# 2_MCU.net
KiCad netlist of a schematic drawn in Altium Designer
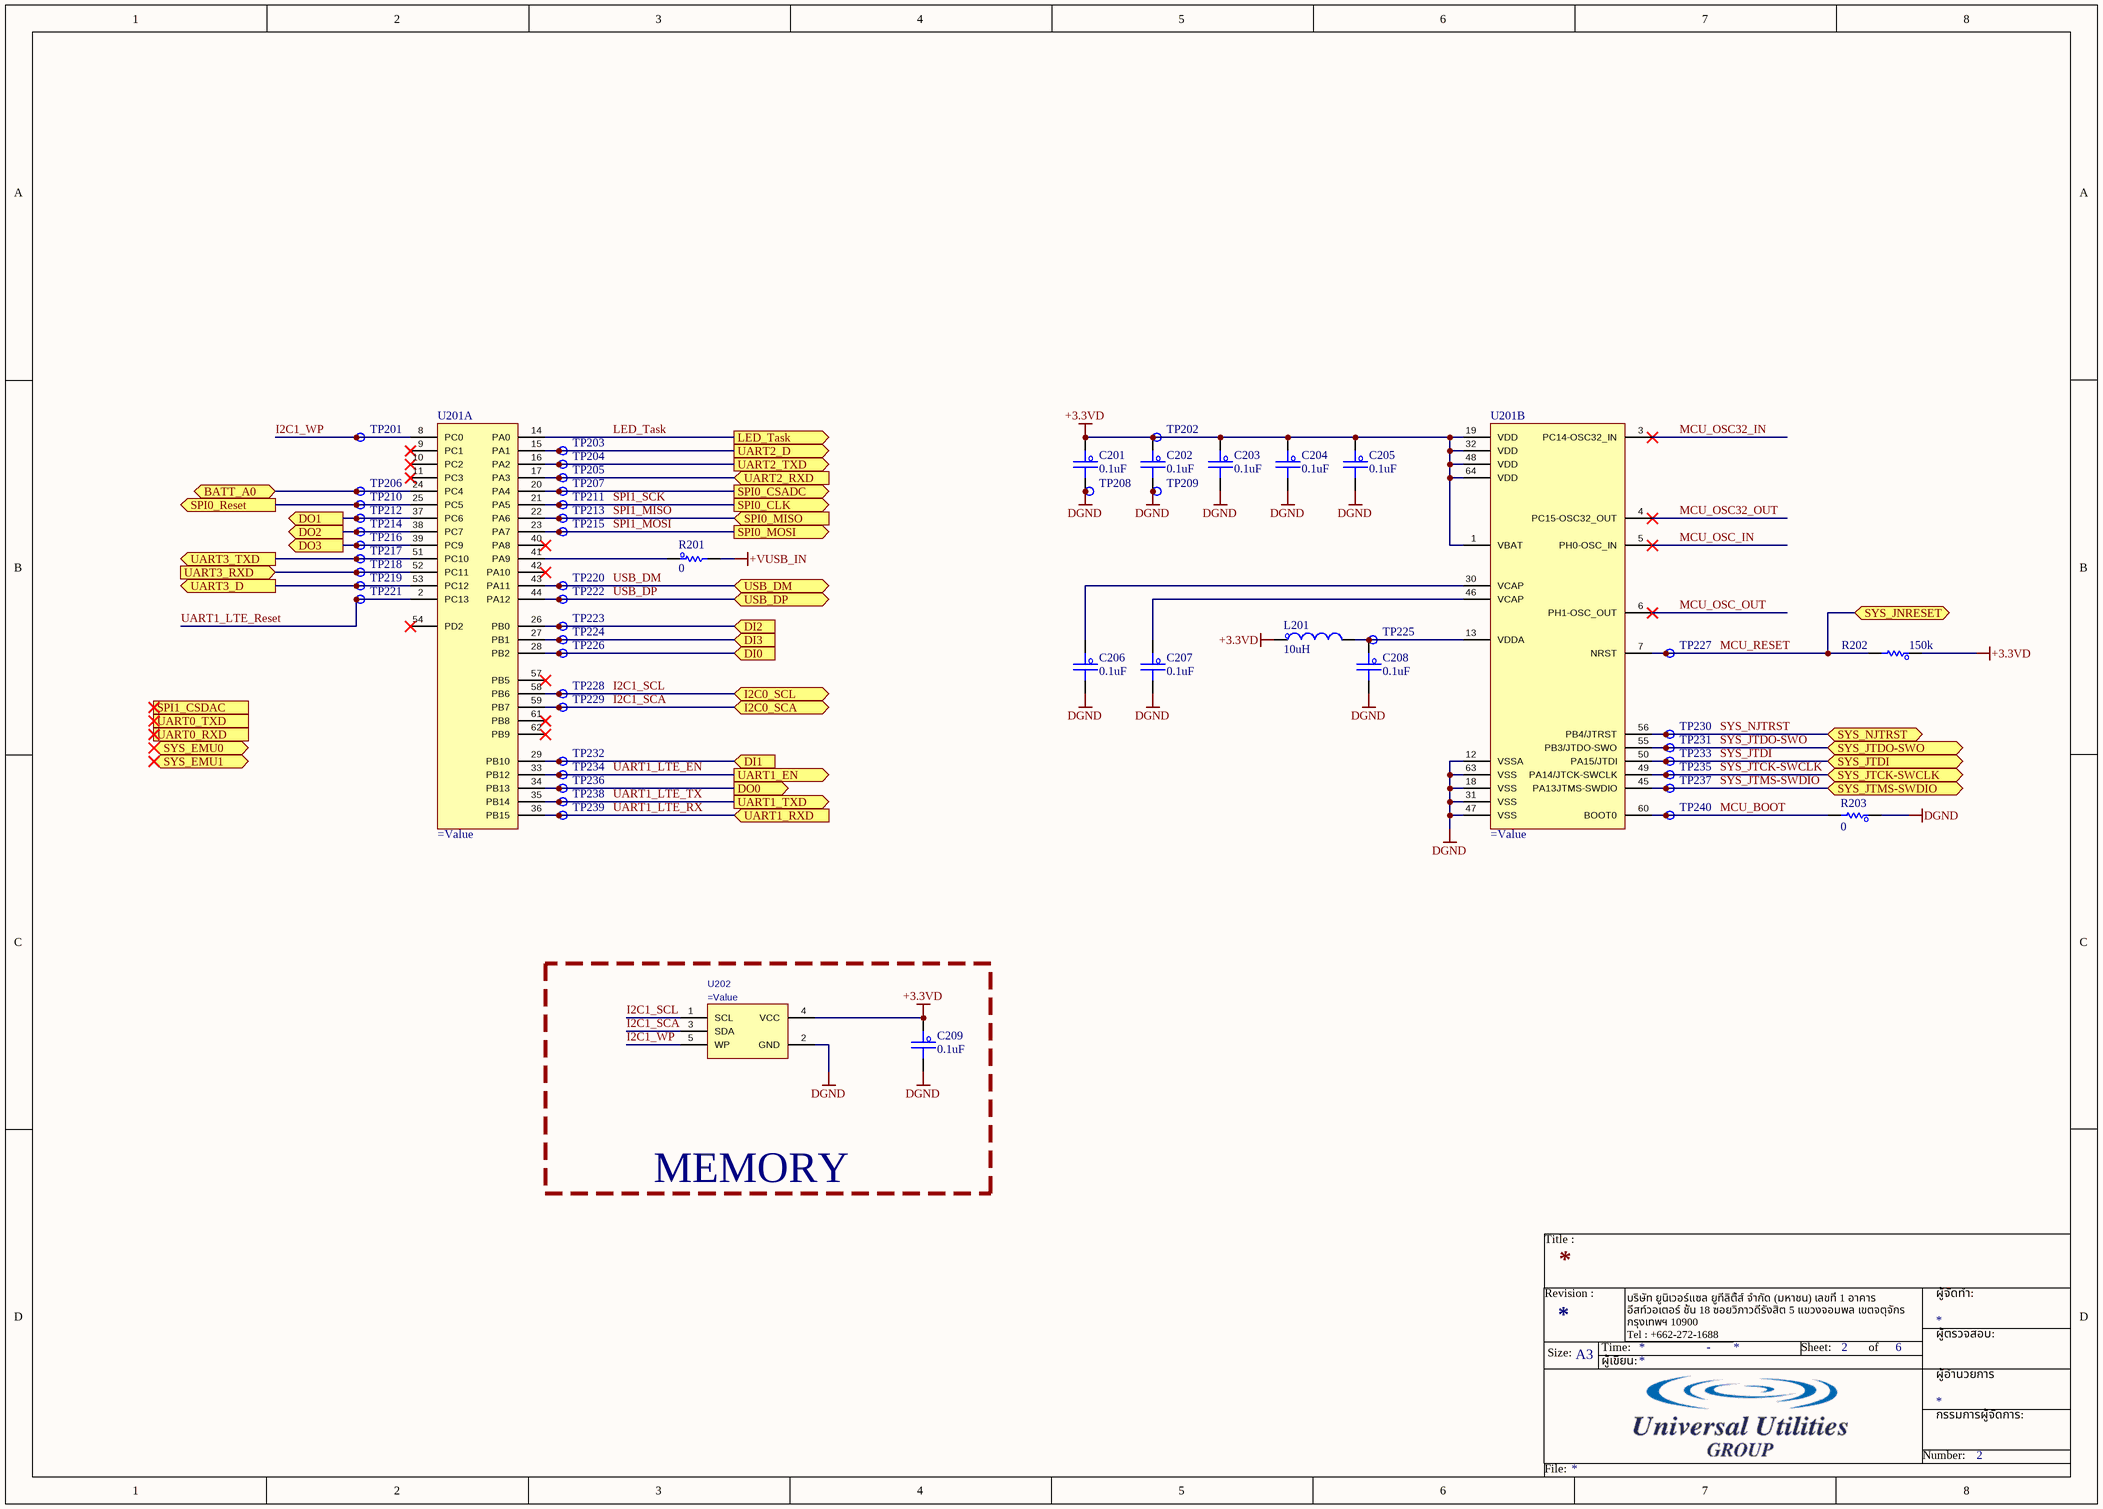
[diagram p0: 2_MCU.SchDoc]

(export (version "E")
  (design (tool "Eeschema 10.0.6"))
  (components
    (comp (ref "C201")
      (value "0.1uF")
      (footprint "C_0603")
      (description "CAP CER 0.1UF 50V X7R 0603")
      (fields (field (name "MANUFACTURER") "KEMET") (field (name "PARTNUMBER") "C0603C104K5RACTU"))
      (libsource (lib "UUSymbol") (part "C_Capacitor"))
    )
    (comp (ref "C202")
      (value "0.1uF")
      (footprint "C_0603")
      (description "CAP CER 0.1UF 50V X7R 0603")
      (fields (field (name "MANUFACTURER") "KEMET") (field (name "PARTNUMBER") "C0603C104K5RACTU"))
      (libsource (lib "UUSymbol") (part "C_Capacitor"))
    )
    (comp (ref "C203")
      (value "0.1uF")
      (footprint "C_0603")
      (description "CAP CER 0.1UF 50V X7R 0603")
      (fields (field (name "MANUFACTURER") "KEMET") (field (name "PARTNUMBER") "C0603C104K5RACTU"))
      (libsource (lib "UUSymbol") (part "C_Capacitor"))
    )
    (comp (ref "C204")
      (value "0.1uF")
      (footprint "C_0603")
      (description "CAP CER 0.1UF 50V X7R 0603")
      (fields (field (name "MANUFACTURER") "KEMET") (field (name "PARTNUMBER") "C0603C104K5RACTU"))
      (libsource (lib "UUSymbol") (part "C_Capacitor"))
    )
    (comp (ref "C205")
      (value "0.1uF")
      (footprint "C_0603")
      (description "CAP CER 0.1UF 50V X7R 0603")
      (fields (field (name "MANUFACTURER") "KEMET") (field (name "PARTNUMBER") "C0603C104K5RACTU"))
      (libsource (lib "UUSymbol") (part "C_Capacitor"))
    )
    (comp (ref "C206")
      (value "0.1uF")
      (footprint "C_0603")
      (description "CAP CER 0.1UF 50V X7R 0603")
      (fields (field (name "MANUFACTURER") "KEMET") (field (name "PARTNUMBER") "C0603C104K5RACTU"))
      (libsource (lib "UUSymbol") (part "C_Capacitor"))
    )
    (comp (ref "C207")
      (value "0.1uF")
      (footprint "C_0603")
      (description "CAP CER 0.1UF 50V X7R 0603")
      (fields (field (name "MANUFACTURER") "KEMET") (field (name "PARTNUMBER") "C0603C104K5RACTU"))
      (libsource (lib "UUSymbol") (part "C_Capacitor"))
    )
    (comp (ref "C208")
      (value "0.1uF")
      (footprint "C_0603")
      (description "CAP CER 0.1UF 50V X7R 0603")
      (fields (field (name "MANUFACTURER") "KEMET") (field (name "PARTNUMBER") "C0603C104K5RACTU"))
      (libsource (lib "UUSymbol") (part "C_Capacitor"))
    )
    (comp (ref "C209")
      (value "0.1uF")
      (footprint "C_0603")
      (description "CAP CER 0.1UF 50V X7R 0603")
      (fields (field (name "MANUFACTURER") "KEMET") (field (name "PARTNUMBER") "C0603C104K5RACTU"))
      (libsource (lib "UUSymbol") (part "C_Capacitor"))
    )
    (comp (ref "L201")
      (value "10uH")
      (footprint "L_0603")
      (description "10µH Shielded Multilayer Inductor 250mA 1.05Ohm 0603 (1608 Metric)")
      (fields (field (name "MANUFACTURER") "TDK Corporation") (field (name "PARTNUMBER") "MLZ1608M100WT000"))
      (libsource (lib "UUSymbol") (part "L_Inductor"))
    )
    (comp (ref "R201")
      (value "0")
      (footprint "R_0603")
      (description "RES SMD 0 OHM JUMP 1/10W 0603")
      (fields (field (name "MANUFACTURER") "Vishay Dale") (field (name "PARTNUMBER") "CRCW06030000Z0EBC"))
      (libsource (lib "UUSymbol") (part "R_Resister"))
    )
    (comp (ref "R202")
      (value "150k")
      (footprint "R_0603")
      (description "RES SMD 150K OHM 1% 1/10W 0603")
      (fields (field (name "MANUFACTURER") "Vishay Dale") (field (name "PARTNUMBER") "CRCW0603150KFKEAC"))
      (libsource (lib "UUSymbol") (part "R_Resister"))
    )
    (comp (ref "R203")
      (value "0")
      (footprint "R_0603")
      (description "RES SMD 0 OHM JUMP 1/10W 0603")
      (fields (field (name "MANUFACTURER") "Vishay Dale") (field (name "PARTNUMBER") "CRCW06030000Z0EBC"))
      (libsource (lib "UUSymbol") (part "R_Resister"))
    )
    (comp (ref "TP201")
      (value "~")
      (footprint "TP_Testpoint")
      (description "TestPoint")
      (libsource (lib "UUSymbol") (part "TP_TestPoint"))
    )
    (comp (ref "TP202")
      (value "~")
      (footprint "TP_Testpoint")
      (description "TestPoint")
      (libsource (lib "UUSymbol") (part "TP_TestPoint"))
    )
    (comp (ref "TP203")
      (value "~")
      (footprint "TP_Testpoint")
      (description "TestPoint")
      (libsource (lib "UUSymbol") (part "TP_TestPoint"))
    )
    (comp (ref "TP204")
      (value "~")
      (footprint "TP_Testpoint")
      (description "TestPoint")
      (libsource (lib "UUSymbol") (part "TP_TestPoint"))
    )
    (comp (ref "TP205")
      (value "~")
      (footprint "TP_Testpoint")
      (description "TestPoint")
      (libsource (lib "UUSymbol") (part "TP_TestPoint"))
    )
    (comp (ref "TP206")
      (value "~")
      (footprint "TP_Testpoint")
      (description "TestPoint")
      (libsource (lib "UUSymbol") (part "TP_TestPoint"))
    )
    (comp (ref "TP207")
      (value "~")
      (footprint "TP_Testpoint")
      (description "TestPoint")
      (libsource (lib "UUSymbol") (part "TP_TestPoint"))
    )
    (comp (ref "TP208")
      (value "~")
      (footprint "TP_Testpoint")
      (description "TestPoint")
      (libsource (lib "UUSymbol") (part "TP_TestPoint"))
    )
    (comp (ref "TP209")
      (value "~")
      (footprint "TP_Testpoint")
      (description "TestPoint")
      (libsource (lib "UUSymbol") (part "TP_TestPoint"))
    )
    (comp (ref "TP210")
      (value "~")
      (footprint "TP_Testpoint")
      (description "TestPoint")
      (libsource (lib "UUSymbol") (part "TP_TestPoint"))
    )
    (comp (ref "TP211")
      (value "~")
      (footprint "TP_Testpoint")
      (description "TestPoint")
      (libsource (lib "UUSymbol") (part "TP_TestPoint"))
    )
    (comp (ref "TP212")
      (value "~")
      (footprint "TP_Testpoint")
      (description "TestPoint")
      (libsource (lib "UUSymbol") (part "TP_TestPoint"))
    )
    (comp (ref "TP213")
      (value "~")
      (footprint "TP_Testpoint")
      (description "TestPoint")
      (libsource (lib "UUSymbol") (part "TP_TestPoint"))
    )
    (comp (ref "TP214")
      (value "~")
      (footprint "TP_Testpoint")
      (description "TestPoint")
      (libsource (lib "UUSymbol") (part "TP_TestPoint"))
    )
    (comp (ref "TP215")
      (value "~")
      (footprint "TP_Testpoint")
      (description "TestPoint")
      (libsource (lib "UUSymbol") (part "TP_TestPoint"))
    )
    (comp (ref "TP216")
      (value "~")
      (footprint "TP_Testpoint")
      (description "TestPoint")
      (libsource (lib "UUSymbol") (part "TP_TestPoint"))
    )
    (comp (ref "TP217")
      (value "~")
      (footprint "TP_Testpoint")
      (description "TestPoint")
      (libsource (lib "UUSymbol") (part "TP_TestPoint"))
    )
    (comp (ref "TP218")
      (value "~")
      (footprint "TP_Testpoint")
      (description "TestPoint")
      (libsource (lib "UUSymbol") (part "TP_TestPoint"))
    )
    (comp (ref "TP219")
      (value "~")
      (footprint "TP_Testpoint")
      (description "TestPoint")
      (libsource (lib "UUSymbol") (part "TP_TestPoint"))
    )
    (comp (ref "TP220")
      (value "~")
      (footprint "TP_Testpoint")
      (description "TestPoint")
      (libsource (lib "UUSymbol") (part "TP_TestPoint"))
    )
    (comp (ref "TP221")
      (value "~")
      (footprint "TP_Testpoint")
      (description "TestPoint")
      (libsource (lib "UUSymbol") (part "TP_TestPoint"))
    )
    (comp (ref "TP222")
      (value "~")
      (footprint "TP_Testpoint")
      (description "TestPoint")
      (libsource (lib "UUSymbol") (part "TP_TestPoint"))
    )
    (comp (ref "TP223")
      (value "~")
      (footprint "TP_Testpoint")
      (description "TestPoint")
      (libsource (lib "UUSymbol") (part "TP_TestPoint"))
    )
    (comp (ref "TP224")
      (value "~")
      (footprint "TP_Testpoint")
      (description "TestPoint")
      (libsource (lib "UUSymbol") (part "TP_TestPoint"))
    )
    (comp (ref "TP225")
      (value "~")
      (footprint "TP_Testpoint")
      (description "TestPoint")
      (libsource (lib "UUSymbol") (part "TP_TestPoint"))
    )
    (comp (ref "TP226")
      (value "~")
      (footprint "TP_Testpoint")
      (description "TestPoint")
      (libsource (lib "UUSymbol") (part "TP_TestPoint"))
    )
    (comp (ref "TP227")
      (value "~")
      (footprint "TP_Testpoint")
      (description "TestPoint")
      (libsource (lib "UUSymbol") (part "TP_TestPoint"))
    )
    (comp (ref "TP228")
      (value "~")
      (footprint "TP_Testpoint")
      (description "TestPoint")
      (libsource (lib "UUSymbol") (part "TP_TestPoint"))
    )
    (comp (ref "TP229")
      (value "~")
      (footprint "TP_Testpoint")
      (description "TestPoint")
      (libsource (lib "UUSymbol") (part "TP_TestPoint"))
    )
    (comp (ref "TP230")
      (value "~")
      (footprint "TP_Testpoint")
      (description "TestPoint")
      (libsource (lib "UUSymbol") (part "TP_TestPoint"))
    )
    (comp (ref "TP231")
      (value "~")
      (footprint "TP_Testpoint")
      (description "TestPoint")
      (libsource (lib "UUSymbol") (part "TP_TestPoint"))
    )
    (comp (ref "TP232")
      (value "~")
      (footprint "TP_Testpoint")
      (description "TestPoint")
      (libsource (lib "UUSymbol") (part "TP_TestPoint"))
    )
    (comp (ref "TP233")
      (value "~")
      (footprint "TP_Testpoint")
      (description "TestPoint")
      (libsource (lib "UUSymbol") (part "TP_TestPoint"))
    )
    (comp (ref "TP234")
      (value "~")
      (footprint "TP_Testpoint")
      (description "TestPoint")
      (libsource (lib "UUSymbol") (part "TP_TestPoint"))
    )
    (comp (ref "TP235")
      (value "~")
      (footprint "TP_Testpoint")
      (description "TestPoint")
      (libsource (lib "UUSymbol") (part "TP_TestPoint"))
    )
    (comp (ref "TP236")
      (value "~")
      (footprint "TP_Testpoint")
      (description "TestPoint")
      (libsource (lib "UUSymbol") (part "TP_TestPoint"))
    )
    (comp (ref "TP237")
      (value "~")
      (footprint "TP_Testpoint")
      (description "TestPoint")
      (libsource (lib "UUSymbol") (part "TP_TestPoint"))
    )
    (comp (ref "TP238")
      (value "~")
      (footprint "TP_Testpoint")
      (description "TestPoint")
      (libsource (lib "UUSymbol") (part "TP_TestPoint"))
    )
    (comp (ref "TP239")
      (value "~")
      (footprint "TP_Testpoint")
      (description "TestPoint")
      (libsource (lib "UUSymbol") (part "TP_TestPoint"))
    )
    (comp (ref "TP240")
      (value "~")
      (footprint "TP_Testpoint")
      (description "TestPoint")
      (libsource (lib "UUSymbol") (part "TP_TestPoint"))
    )
    (comp (ref "U201")
      (value "~")
      (footprint "LQFP64")
      (description "IC MCU 32BIT 1376KB FLSH 64LQFP")
      (fields (field (name "PARTNUMBER") "STM32H7A3RGT6") (field (name "MANUFACTURER") "STMicroelectronics"))
      (libsource (lib "UUSymbol") (part "IC_MCU_STM32H7A3RGT6"))
    )
    (comp (ref "U202")
      (value "~")
      (footprint "SOT65P210X110-5N")
      (description "IC EEPROM 2KBIT I2C SC70-5")
      (fields
        (field (name "MANUFACTURER") "Microchip Technology")
        (field (name "PARTNUMBER") "24AA02HT-I/LT")
      )
      (libsource (lib "UUSymbol") (part "IC_MEM_24AA02HT"))
    )
  )
  (nets
    (net (code "1") (name "+3.3VD") (class "Default")
      (node (ref "C201") (pin "1") (pinfunction "1_1") (pintype "passive"))
      (node (ref "C202") (pin "1") (pinfunction "1_1") (pintype "passive"))
      (node (ref "C203") (pin "1") (pinfunction "1_1") (pintype "passive"))
      (node (ref "C204") (pin "1") (pinfunction "1_1") (pintype "passive"))
      (node (ref "C205") (pin "1") (pinfunction "1_1") (pintype "passive"))
      (node (ref "C209") (pin "1") (pinfunction "1_1") (pintype "passive"))
      (node (ref "L201") (pin "1") (pinfunction "1_1") (pintype "passive"))
      (node (ref "R202") (pin "1") (pinfunction "1_1") (pintype "passive"))
      (node (ref "TP202") (pin "1") (pinfunction "1_1") (pintype "passive"))
      (node (ref "U201") (pin "1") (pinfunction "VBAT_1") (pintype "passive"))
      (node (ref "U201") (pin "19") (pinfunction "VDD_19") (pintype "passive"))
      (node (ref "U201") (pin "32") (pinfunction "VDD_32") (pintype "passive"))
      (node (ref "U201") (pin "48") (pinfunction "VDD_48") (pintype "passive"))
      (node (ref "U201") (pin "64") (pinfunction "VDD_64") (pintype "passive"))
      (node (ref "U202") (pin "4") (pinfunction "VCC_4") (pintype "passive"))
    )
    (net (code "2") (name "+VUSB_IN") (class "Default")
      (node (ref "R201") (pin "2") (pinfunction "2_2") (pintype "passive"))
    )
    (net (code "3") (name "/BATT_A0") (class "Default")
      (node (ref "TP206") (pin "1") (pinfunction "1_1") (pintype "passive"))
      (node (ref "U201") (pin "24") (pinfunction "PC4_24") (pintype "passive"))
    )
    (net (code "4") (name "/DI0") (class "Default")
      (node (ref "TP226") (pin "1") (pinfunction "1_1") (pintype "passive"))
      (node (ref "U201") (pin "28") (pinfunction "PB2_28") (pintype "passive"))
    )
    (net (code "5") (name "/DI1") (class "Default")
      (node (ref "TP232") (pin "1") (pinfunction "1_1") (pintype "passive"))
      (node (ref "U201") (pin "29") (pinfunction "PB10_29") (pintype "passive"))
    )
    (net (code "6") (name "/DI2") (class "Default")
      (node (ref "TP223") (pin "1") (pinfunction "1_1") (pintype "passive"))
      (node (ref "U201") (pin "26") (pinfunction "PB0_26") (pintype "passive"))
    )
    (net (code "7") (name "/DI3") (class "Default")
      (node (ref "TP224") (pin "1") (pinfunction "1_1") (pintype "passive"))
      (node (ref "U201") (pin "27") (pinfunction "PB1_27") (pintype "passive"))
    )
    (net (code "8") (name "/DO0") (class "Default")
      (node (ref "TP236") (pin "1") (pinfunction "1_1") (pintype "passive"))
      (node (ref "U201") (pin "34") (pinfunction "PB13_34") (pintype "passive"))
    )
    (net (code "9") (name "/DO1") (class "Default")
      (node (ref "TP212") (pin "1") (pinfunction "1_1") (pintype "passive"))
      (node (ref "U201") (pin "37") (pinfunction "PC6_37") (pintype "passive"))
    )
    (net (code "10") (name "/DO2") (class "Default")
      (node (ref "TP214") (pin "1") (pinfunction "1_1") (pintype "passive"))
      (node (ref "U201") (pin "38") (pinfunction "PC7_38") (pintype "passive"))
    )
    (net (code "11") (name "/DO3") (class "Default")
      (node (ref "TP216") (pin "1") (pinfunction "1_1") (pintype "passive"))
      (node (ref "U201") (pin "39") (pinfunction "PC9_39") (pintype "passive"))
    )
    (net (code "12") (name "/I2C1_SCA") (class "Default")
      (node (ref "TP229") (pin "1") (pinfunction "1_1") (pintype "passive"))
      (node (ref "U201") (pin "59") (pinfunction "PB7_59") (pintype "passive"))
      (node (ref "U202") (pin "3") (pinfunction "SDA_3") (pintype "passive"))
    )
    (net (code "13") (name "/I2C1_SCL") (class "Default")
      (node (ref "TP228") (pin "1") (pinfunction "1_1") (pintype "passive"))
      (node (ref "U201") (pin "58") (pinfunction "PB6_58") (pintype "passive"))
      (node (ref "U202") (pin "1") (pinfunction "SCL_1") (pintype "passive"))
    )
    (net (code "14") (name "/I2C1_WP") (class "Default")
      (node (ref "TP201") (pin "1") (pinfunction "1_1") (pintype "passive"))
      (node (ref "U201") (pin "8") (pinfunction "PC0_8") (pintype "passive"))
      (node (ref "U202") (pin "5") (pinfunction "WP_5") (pintype "passive"))
    )
    (net (code "15") (name "/LED_Task") (class "Default")
      (node (ref "U201") (pin "14") (pinfunction "PA0_14") (pintype "passive"))
    )
    (net (code "16") (name "/MCU_BOOT") (class "Default")
      (node (ref "R203") (pin "2") (pinfunction "2_2") (pintype "passive"))
      (node (ref "TP240") (pin "1") (pinfunction "1_1") (pintype "passive"))
      (node (ref "U201") (pin "60") (pinfunction "BOOT0_60") (pintype "passive"))
    )
    (net (code "17") (name "/MCU_OSC32_IN") (class "Default")
      (node (ref "U201") (pin "3") (pinfunction "PC14-OSC32_IN_3") (pintype "passive+no_connect"))
    )
    (net (code "18") (name "/MCU_OSC32_OUT") (class "Default")
      (node (ref "U201") (pin "4") (pinfunction "PC15-OSC32_OUT_4") (pintype "passive+no_connect"))
    )
    (net (code "19") (name "/MCU_OSC_IN") (class "Default")
      (node (ref "U201") (pin "5") (pinfunction "PH0-OSC_IN_5") (pintype "passive+no_connect"))
    )
    (net (code "20") (name "/MCU_OSC_OUT") (class "Default")
      (node (ref "U201") (pin "6") (pinfunction "PH1-OSC_OUT_6") (pintype "passive+no_connect"))
    )
    (net (code "21") (name "/MCU_RESET") (class "Default")
      (node (ref "R202") (pin "2") (pinfunction "2_2") (pintype "passive"))
      (node (ref "TP227") (pin "1") (pinfunction "1_1") (pintype "passive"))
      (node (ref "U201") (pin "7") (pinfunction "NRST_7") (pintype "passive"))
    )
    (net (code "22") (name "/SPI0_CSADC") (class "Default")
      (node (ref "TP207") (pin "1") (pinfunction "1_1") (pintype "passive"))
      (node (ref "U201") (pin "20") (pinfunction "PA4_20") (pintype "passive"))
    )
    (net (code "23") (name "/SPI0_Reset") (class "Default")
      (node (ref "TP210") (pin "1") (pinfunction "1_1") (pintype "passive"))
      (node (ref "U201") (pin "25") (pinfunction "PC5_25") (pintype "passive"))
    )
    (net (code "25") (name "/SPI1_MISO") (class "Default")
      (node (ref "TP213") (pin "1") (pinfunction "1_1") (pintype "passive"))
      (node (ref "U201") (pin "22") (pinfunction "PA6_22") (pintype "passive"))
    )
    (net (code "26") (name "/SPI1_MOSI") (class "Default")
      (node (ref "TP215") (pin "1") (pinfunction "1_1") (pintype "passive"))
      (node (ref "U201") (pin "23") (pinfunction "PA7_23") (pintype "passive"))
    )
    (net (code "27") (name "/SPI1_SCK") (class "Default")
      (node (ref "TP211") (pin "1") (pinfunction "1_1") (pintype "passive"))
      (node (ref "U201") (pin "21") (pinfunction "PA5_21") (pintype "passive"))
    )
    (net (code "30") (name "/SYS_JTCK-SWCLK") (class "Default")
      (node (ref "TP235") (pin "1") (pinfunction "1_1") (pintype "passive"))
      (node (ref "U201") (pin "49") (pinfunction "PA14/JTCK-SWCLK_49") (pintype "passive"))
    )
    (net (code "31") (name "/SYS_JTDI") (class "Default")
      (node (ref "TP233") (pin "1") (pinfunction "1_1") (pintype "passive"))
      (node (ref "U201") (pin "50") (pinfunction "PA15/JTDI_50") (pintype "passive"))
    )
    (net (code "32") (name "/SYS_JTDO-SWO") (class "Default")
      (node (ref "TP231") (pin "1") (pinfunction "1_1") (pintype "passive"))
      (node (ref "U201") (pin "55") (pinfunction "PB3/JTDO-SWO_55") (pintype "passive"))
    )
    (net (code "33") (name "/SYS_JTMS-SWDIO") (class "Default")
      (node (ref "TP237") (pin "1") (pinfunction "1_1") (pintype "passive"))
      (node (ref "U201") (pin "45") (pinfunction "PA13JTMS-SWDIO_45") (pintype "passive"))
    )
    (net (code "34") (name "/SYS_NJTRST") (class "Default")
      (node (ref "TP230") (pin "1") (pinfunction "1_1") (pintype "passive"))
      (node (ref "U201") (pin "56") (pinfunction "PB4/JTRST_56") (pintype "passive"))
    )
    (net (code "37") (name "/UART1_LTE_EN") (class "Default")
      (node (ref "TP234") (pin "1") (pinfunction "1_1") (pintype "passive"))
      (node (ref "U201") (pin "33") (pinfunction "PB12_33") (pintype "passive"))
    )
    (net (code "38") (name "/UART1_LTE_RX") (class "Default")
      (node (ref "TP239") (pin "1") (pinfunction "1_1") (pintype "passive"))
      (node (ref "U201") (pin "36") (pinfunction "PB15_36") (pintype "passive"))
    )
    (net (code "39") (name "/UART1_LTE_Reset") (class "Default")
      (node (ref "TP221") (pin "1") (pinfunction "1_1") (pintype "passive"))
      (node (ref "U201") (pin "2") (pinfunction "PC13_2") (pintype "passive"))
    )
    (net (code "40") (name "/UART1_LTE_TX") (class "Default")
      (node (ref "TP238") (pin "1") (pinfunction "1_1") (pintype "passive"))
      (node (ref "U201") (pin "35") (pinfunction "PB14_35") (pintype "passive"))
    )
    (net (code "41") (name "/UART2_D") (class "Default")
      (node (ref "TP203") (pin "1") (pinfunction "1_1") (pintype "passive"))
      (node (ref "U201") (pin "15") (pinfunction "PA1_15") (pintype "passive"))
    )
    (net (code "42") (name "/UART2_RXD") (class "Default")
      (node (ref "TP205") (pin "1") (pinfunction "1_1") (pintype "passive"))
      (node (ref "U201") (pin "17") (pinfunction "PA3_17") (pintype "passive"))
    )
    (net (code "43") (name "/UART2_TXD") (class "Default")
      (node (ref "TP204") (pin "1") (pinfunction "1_1") (pintype "passive"))
      (node (ref "U201") (pin "16") (pinfunction "PA2_16") (pintype "passive"))
    )
    (net (code "44") (name "/UART3_D") (class "Default")
      (node (ref "TP219") (pin "1") (pinfunction "1_1") (pintype "passive"))
      (node (ref "U201") (pin "53") (pinfunction "PC12_53") (pintype "passive"))
    )
    (net (code "45") (name "/UART3_RXD") (class "Default")
      (node (ref "TP218") (pin "1") (pinfunction "1_1") (pintype "passive"))
      (node (ref "U201") (pin "52") (pinfunction "PC11_52") (pintype "passive"))
    )
    (net (code "46") (name "/UART3_TXD") (class "Default")
      (node (ref "TP217") (pin "1") (pinfunction "1_1") (pintype "passive"))
      (node (ref "U201") (pin "51") (pinfunction "PC10_51") (pintype "passive"))
    )
    (net (code "47") (name "/USB_DM") (class "Default")
      (node (ref "TP220") (pin "1") (pinfunction "1_1") (pintype "passive"))
      (node (ref "U201") (pin "43") (pinfunction "PA11_43") (pintype "passive"))
    )
    (net (code "48") (name "/USB_DP") (class "Default")
      (node (ref "TP222") (pin "1") (pinfunction "1_1") (pintype "passive"))
      (node (ref "U201") (pin "44") (pinfunction "PA12_44") (pintype "passive"))
    )
    (net (code "49") (name "DGND") (class "Default")
      (node (ref "C201") (pin "2") (pinfunction "2_2") (pintype "passive"))
      (node (ref "C202") (pin "2") (pinfunction "2_2") (pintype "passive"))
      (node (ref "C203") (pin "2") (pinfunction "2_2") (pintype "passive"))
      (node (ref "C204") (pin "2") (pinfunction "2_2") (pintype "passive"))
      (node (ref "C205") (pin "2") (pinfunction "2_2") (pintype "passive"))
      (node (ref "C206") (pin "2") (pinfunction "2_2") (pintype "passive"))
      (node (ref "C207") (pin "2") (pinfunction "2_2") (pintype "passive"))
      (node (ref "C208") (pin "2") (pinfunction "2_2") (pintype "passive"))
      (node (ref "C209") (pin "2") (pinfunction "2_2") (pintype "passive"))
      (node (ref "R203") (pin "1") (pinfunction "1_1") (pintype "passive"))
      (node (ref "TP208") (pin "1") (pinfunction "1_1") (pintype "passive"))
      (node (ref "TP209") (pin "1") (pinfunction "1_1") (pintype "passive"))
      (node (ref "U201") (pin "12") (pinfunction "VSSA_12") (pintype "passive"))
      (node (ref "U201") (pin "18") (pinfunction "VSS_18") (pintype "passive"))
      (node (ref "U201") (pin "31") (pinfunction "VSS_31") (pintype "passive"))
      (node (ref "U201") (pin "47") (pinfunction "VSS_47") (pintype "passive"))
      (node (ref "U201") (pin "63") (pinfunction "VSS_63") (pintype "passive"))
      (node (ref "U202") (pin "2") (pinfunction "GND_2") (pintype "passive"))
    )
    (net (code "50") (name "Net-(C206-Pad1)") (class "Default")
      (node (ref "C206") (pin "1") (pinfunction "1_1") (pintype "passive"))
      (node (ref "U201") (pin "30") (pinfunction "VCAP_30") (pintype "passive"))
    )
    (net (code "51") (name "Net-(C207-Pad1)") (class "Default")
      (node (ref "C207") (pin "1") (pinfunction "1_1") (pintype "passive"))
      (node (ref "U201") (pin "46") (pinfunction "VCAP_46") (pintype "passive"))
    )
    (net (code "52") (name "Net-(U201A-PA9)") (class "Default")
      (node (ref "R201") (pin "1") (pinfunction "1_1") (pintype "passive"))
      (node (ref "U201") (pin "41") (pinfunction "PA9_41") (pintype "passive"))
    )
    (net (code "53") (name "Net-(U201B-VDDA)") (class "Default")
      (node (ref "C208") (pin "1") (pinfunction "1_1") (pintype "passive"))
      (node (ref "L201") (pin "2") (pinfunction "2_2") (pintype "passive"))
      (node (ref "TP225") (pin "1") (pinfunction "1_1") (pintype "passive"))
      (node (ref "U201") (pin "13") (pinfunction "VDDA_13") (pintype "passive"))
    )
    (net (code "54") (name "unconnected-(U201A-PA8-Pad40)") (class "Default")
      (node (ref "U201") (pin "40") (pinfunction "PA8_40") (pintype "passive+no_connect"))
    )
    (net (code "55") (name "unconnected-(U201A-PA10-Pad42)") (class "Default")
      (node (ref "U201") (pin "42") (pinfunction "PA10_42") (pintype "passive+no_connect"))
    )
    (net (code "56") (name "unconnected-(U201A-PB5-Pad57)") (class "Default")
      (node (ref "U201") (pin "57") (pinfunction "PB5_57") (pintype "passive+no_connect"))
    )
    (net (code "57") (name "unconnected-(U201A-PB8-Pad61)") (class "Default")
      (node (ref "U201") (pin "61") (pinfunction "PB8_61") (pintype "passive+no_connect"))
    )
    (net (code "58") (name "unconnected-(U201A-PB9-Pad62)") (class "Default")
      (node (ref "U201") (pin "62") (pinfunction "PB9_62") (pintype "passive+no_connect"))
    )
    (net (code "59") (name "unconnected-(U201A-PC1-Pad9)") (class "Default")
      (node (ref "U201") (pin "9") (pinfunction "PC1_9") (pintype "passive+no_connect"))
    )
    (net (code "60") (name "unconnected-(U201A-PC2-Pad10)") (class "Default")
      (node (ref "U201") (pin "10") (pinfunction "PC2_10") (pintype "passive+no_connect"))
    )
    (net (code "61") (name "unconnected-(U201A-PC3-Pad11)") (class "Default")
      (node (ref "U201") (pin "11") (pinfunction "PC3_11") (pintype "passive+no_connect"))
    )
    (net (code "62") (name "unconnected-(U201A-PD2-Pad54)") (class "Default")
      (node (ref "U201") (pin "54") (pinfunction "PD2_54") (pintype "passive+no_connect"))
    )
  )
)
